# Sch_Lab_2.net
KiCad netlist of a schematic drawn in Altium Designer
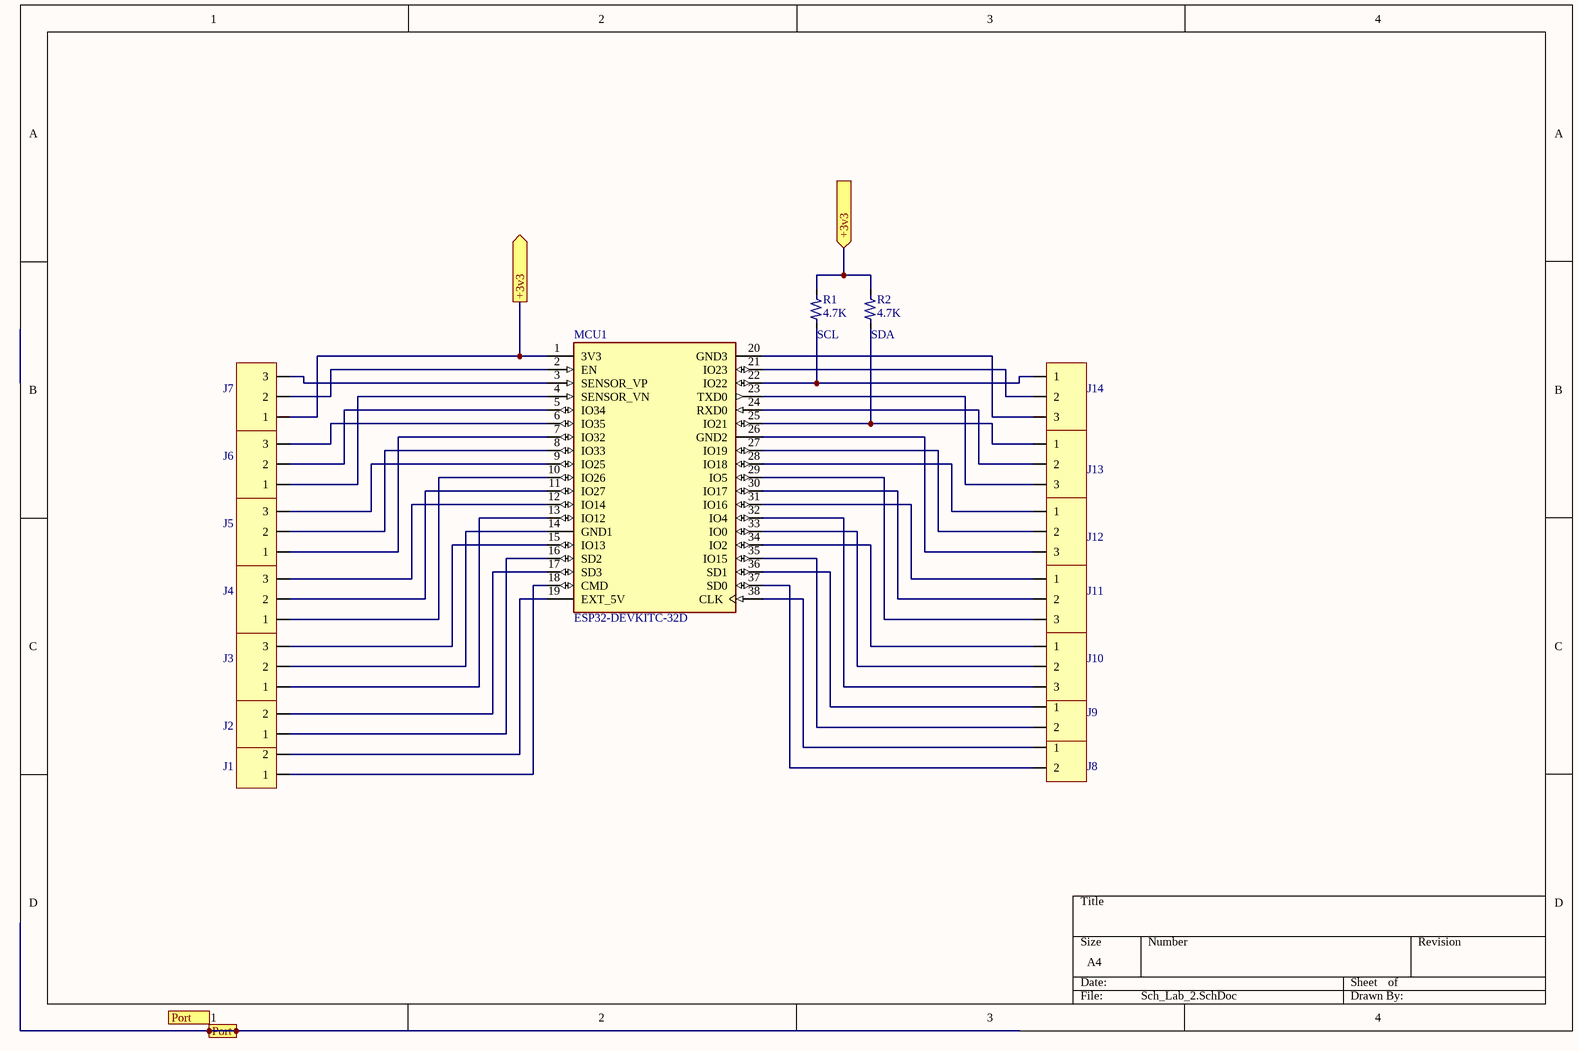
[diagram p0: Sch_Lab_2.SchDoc]

(export (version "E")
  (design (tool "Eeschema 10.0.6"))
  (components
    (comp (ref "J1") (value "~") (footprint "TB_200Mil 2 P") (libsource (lib "") (part "TB 2 PIN_1")))
    (comp (ref "J2") (value "~") (footprint "TB_200Mil 2 P") (libsource (lib "") (part "TB 2 PIN_1")))
    (comp (ref "J3") (value "~") (footprint "TB_200Mil 3 P") (libsource (lib "") (part "TB 3 PIN_1")))
    (comp (ref "J4") (value "~") (footprint "TB_200Mil 3 P") (libsource (lib "") (part "TB 3 PIN_1")))
    (comp (ref "J5") (value "~") (footprint "TB_200Mil 3 P") (libsource (lib "") (part "TB 3 PIN_1")))
    (comp (ref "J6") (value "~") (footprint "TB_200Mil 3 P") (libsource (lib "") (part "TB 3 PIN_1")))
    (comp (ref "J7") (value "~") (footprint "TB_200Mil 3 P") (libsource (lib "") (part "TB 3 PIN_1")))
    (comp (ref "J8")
      (value "~")
      (footprint "TB_200Mil 2 P")
      (libsource (lib "Library Connector") (part "TB 2 PIN"))
    )
    (comp (ref "J9")
      (value "~")
      (footprint "TB_200Mil 2 P")
      (libsource (lib "Library Connector") (part "TB 2 PIN"))
    )
    (comp (ref "J10")
      (value "~")
      (footprint "TB_200Mil 3 P")
      (libsource (lib "Library Connector") (part "TB 3 PIN"))
    )
    (comp (ref "J11")
      (value "~")
      (footprint "TB_200Mil 3 P")
      (libsource (lib "Library Connector") (part "TB 3 PIN"))
    )
    (comp (ref "J12")
      (value "~")
      (footprint "TB_200Mil 3 P")
      (libsource (lib "Library Connector") (part "TB 3 PIN"))
    )
    (comp (ref "J13")
      (value "~")
      (footprint "TB_200Mil 3 P")
      (libsource (lib "Library Connector") (part "TB 3 PIN"))
    )
    (comp (ref "J14")
      (value "~")
      (footprint "TB_200Mil 3 P")
      (libsource (lib "Library Connector") (part "TB 3 PIN"))
    )
    (comp (ref "MCU1")
      (value "ESP32-DEVKITC-32D")
      (footprint "MODULE_ESP32-DEVKITC-32D")
      (description "EVAL BOARD FOR ESP-WROOM-32")
      (fields (field (name "MF") "Espressif Systems"))
      (libsource (lib "ESP32-DEVKITC-32D") (part "ESP32-DEVKITC-32D"))
    )
    (comp (ref "R1") (value "4.7K") (footprint "4.7K") (libsource (lib "Library 0.25w 1_") (part "4.7K")))
    (comp (ref "R2") (value "4.7K") (footprint "4.7K") (libsource (lib "Library 0.25w 1_") (part "4.7K")))
  )
  (nets
    (net (code "1") (name "/+3v3") (class "Default")
      (node (ref "J7") (pin "1") (pinfunction "1_1") (pintype "passive"))
      (node (ref "MCU1") (pin "1") (pinfunction "3V3_1") (pintype "power_in"))
      (node (ref "R1") (pin "2") (pintype "passive"))
      (node (ref "R2") (pin "2") (pintype "passive"))
    )
    (net (code "3") (name "Net-(MCU1-CLK)") (class "Default")
      (node (ref "J8") (pin "1") (pinfunction "1_1") (pintype "passive"))
      (node (ref "MCU1") (pin "38") (pinfunction "CLK_38") (pintype "input"))
    )
    (net (code "4") (name "Net-(MCU1-CMD)") (class "Default")
      (node (ref "J1") (pin "1") (pinfunction "1_1") (pintype "passive"))
      (node (ref "MCU1") (pin "18") (pinfunction "CMD_18") (pintype "bidirectional"))
    )
    (net (code "5") (name "Net-(MCU1-EN)") (class "Default")
      (node (ref "J7") (pin "2") (pinfunction "2_2") (pintype "passive"))
      (node (ref "MCU1") (pin "2") (pinfunction "EN_2") (pintype "input"))
    )
    (net (code "6") (name "Net-(MCU1-EXT_5V)") (class "Default")
      (node (ref "J1") (pin "2") (pinfunction "2_2") (pintype "passive"))
      (node (ref "MCU1") (pin "19") (pinfunction "EXT_5V_19") (pintype "power_in"))
    )
    (net (code "7") (name "Net-(MCU1-GND1)") (class "Default")
      (node (ref "J3") (pin "2") (pinfunction "2_2") (pintype "passive"))
      (node (ref "MCU1") (pin "14") (pinfunction "GND1_14") (pintype "power_in"))
    )
    (net (code "8") (name "Net-(MCU1-GND2)") (class "Default")
      (node (ref "J12") (pin "3") (pinfunction "3_3") (pintype "passive"))
      (node (ref "MCU1") (pin "26") (pinfunction "GND2_26") (pintype "power_in"))
    )
    (net (code "9") (name "Net-(MCU1-GND3)") (class "Default")
      (node (ref "J14") (pin "3") (pinfunction "3_3") (pintype "passive"))
      (node (ref "MCU1") (pin "20") (pinfunction "GND3_20") (pintype "power_in"))
    )
    (net (code "10") (name "Net-(MCU1-IO0)") (class "Default")
      (node (ref "J10") (pin "2") (pinfunction "2_2") (pintype "passive"))
      (node (ref "MCU1") (pin "33") (pinfunction "IO0_33") (pintype "bidirectional"))
    )
    (net (code "11") (name "Net-(MCU1-IO2)") (class "Default")
      (node (ref "J10") (pin "1") (pinfunction "1_1") (pintype "passive"))
      (node (ref "MCU1") (pin "34") (pinfunction "IO2_34") (pintype "bidirectional"))
    )
    (net (code "12") (name "Net-(MCU1-IO4)") (class "Default")
      (node (ref "J10") (pin "3") (pinfunction "3_3") (pintype "passive"))
      (node (ref "MCU1") (pin "32") (pinfunction "IO4_32") (pintype "bidirectional"))
    )
    (net (code "13") (name "Net-(MCU1-IO5)") (class "Default")
      (node (ref "J11") (pin "3") (pinfunction "3_3") (pintype "passive"))
      (node (ref "MCU1") (pin "29") (pinfunction "IO5_29") (pintype "bidirectional"))
    )
    (net (code "14") (name "Net-(MCU1-IO12)") (class "Default")
      (node (ref "J3") (pin "1") (pinfunction "1_1") (pintype "passive"))
      (node (ref "MCU1") (pin "13") (pinfunction "IO12_13") (pintype "bidirectional"))
    )
    (net (code "15") (name "Net-(MCU1-IO13)") (class "Default")
      (node (ref "J3") (pin "3") (pinfunction "3_3") (pintype "passive"))
      (node (ref "MCU1") (pin "15") (pinfunction "IO13_15") (pintype "bidirectional"))
    )
    (net (code "16") (name "Net-(MCU1-IO14)") (class "Default")
      (node (ref "J4") (pin "3") (pinfunction "3_3") (pintype "passive"))
      (node (ref "MCU1") (pin "12") (pinfunction "IO14_12") (pintype "bidirectional"))
    )
    (net (code "17") (name "Net-(MCU1-IO15)") (class "Default")
      (node (ref "J9") (pin "2") (pinfunction "2_2") (pintype "passive"))
      (node (ref "MCU1") (pin "35") (pinfunction "IO15_35") (pintype "bidirectional"))
    )
    (net (code "18") (name "Net-(MCU1-IO16)") (class "Default")
      (node (ref "J11") (pin "1") (pinfunction "1_1") (pintype "passive"))
      (node (ref "MCU1") (pin "31") (pinfunction "IO16_31") (pintype "bidirectional"))
    )
    (net (code "19") (name "Net-(MCU1-IO17)") (class "Default")
      (node (ref "J11") (pin "2") (pinfunction "2_2") (pintype "passive"))
      (node (ref "MCU1") (pin "30") (pinfunction "IO17_30") (pintype "bidirectional"))
    )
    (net (code "20") (name "Net-(MCU1-IO18)") (class "Default")
      (node (ref "J12") (pin "1") (pinfunction "1_1") (pintype "passive"))
      (node (ref "MCU1") (pin "28") (pinfunction "IO18_28") (pintype "bidirectional"))
    )
    (net (code "21") (name "Net-(MCU1-IO19)") (class "Default")
      (node (ref "J12") (pin "2") (pinfunction "2_2") (pintype "passive"))
      (node (ref "MCU1") (pin "27") (pinfunction "IO19_27") (pintype "bidirectional"))
    )
    (net (code "22") (name "Net-(MCU1-IO21)") (class "Default")
      (node (ref "J13") (pin "1") (pinfunction "1_1") (pintype "passive"))
      (node (ref "MCU1") (pin "25") (pinfunction "IO21_25") (pintype "bidirectional"))
      (node (ref "R2") (pin "1") (pintype "passive"))
    )
    (net (code "23") (name "Net-(MCU1-IO22)") (class "Default")
      (node (ref "J14") (pin "1") (pinfunction "1_1") (pintype "passive"))
      (node (ref "MCU1") (pin "22") (pinfunction "IO22_22") (pintype "bidirectional"))
      (node (ref "R1") (pin "1") (pintype "passive"))
    )
    (net (code "24") (name "Net-(MCU1-IO23)") (class "Default")
      (node (ref "J14") (pin "2") (pinfunction "2_2") (pintype "passive"))
      (node (ref "MCU1") (pin "21") (pinfunction "IO23_21") (pintype "bidirectional"))
    )
    (net (code "25") (name "Net-(MCU1-IO25)") (class "Default")
      (node (ref "J5") (pin "3") (pinfunction "3_3") (pintype "passive"))
      (node (ref "MCU1") (pin "9") (pinfunction "IO25_9") (pintype "bidirectional"))
    )
    (net (code "26") (name "Net-(MCU1-IO26)") (class "Default")
      (node (ref "J4") (pin "1") (pinfunction "1_1") (pintype "passive"))
      (node (ref "MCU1") (pin "10") (pinfunction "IO26_10") (pintype "bidirectional"))
    )
    (net (code "27") (name "Net-(MCU1-IO27)") (class "Default")
      (node (ref "J4") (pin "2") (pinfunction "2_2") (pintype "passive"))
      (node (ref "MCU1") (pin "11") (pinfunction "IO27_11") (pintype "bidirectional"))
    )
    (net (code "28") (name "Net-(MCU1-IO32)") (class "Default")
      (node (ref "J5") (pin "1") (pinfunction "1_1") (pintype "passive"))
      (node (ref "MCU1") (pin "7") (pinfunction "IO32_7") (pintype "bidirectional"))
    )
    (net (code "29") (name "Net-(MCU1-IO33)") (class "Default")
      (node (ref "J5") (pin "2") (pinfunction "2_2") (pintype "passive"))
      (node (ref "MCU1") (pin "8") (pinfunction "IO33_8") (pintype "bidirectional"))
    )
    (net (code "30") (name "Net-(MCU1-IO34)") (class "Default")
      (node (ref "J6") (pin "2") (pinfunction "2_2") (pintype "passive"))
      (node (ref "MCU1") (pin "5") (pinfunction "IO34_5") (pintype "bidirectional"))
    )
    (net (code "31") (name "Net-(MCU1-IO35)") (class "Default")
      (node (ref "J6") (pin "3") (pinfunction "3_3") (pintype "passive"))
      (node (ref "MCU1") (pin "6") (pinfunction "IO35_6") (pintype "bidirectional"))
    )
    (net (code "32") (name "Net-(MCU1-RXD0)") (class "Default")
      (node (ref "J13") (pin "2") (pinfunction "2_2") (pintype "passive"))
      (node (ref "MCU1") (pin "24") (pinfunction "RXD0_24") (pintype "input"))
    )
    (net (code "33") (name "Net-(MCU1-SD0)") (class "Default")
      (node (ref "J8") (pin "2") (pinfunction "2_2") (pintype "passive"))
      (node (ref "MCU1") (pin "37") (pinfunction "SD0_37") (pintype "bidirectional"))
    )
    (net (code "34") (name "Net-(MCU1-SD1)") (class "Default")
      (node (ref "J9") (pin "1") (pinfunction "1_1") (pintype "passive"))
      (node (ref "MCU1") (pin "36") (pinfunction "SD1_36") (pintype "bidirectional"))
    )
    (net (code "35") (name "Net-(MCU1-SD2)") (class "Default")
      (node (ref "J2") (pin "1") (pinfunction "1_1") (pintype "passive"))
      (node (ref "MCU1") (pin "16") (pinfunction "SD2_16") (pintype "bidirectional"))
    )
    (net (code "36") (name "Net-(MCU1-SD3)") (class "Default")
      (node (ref "J2") (pin "2") (pinfunction "2_2") (pintype "passive"))
      (node (ref "MCU1") (pin "17") (pinfunction "SD3_17") (pintype "bidirectional"))
    )
    (net (code "37") (name "Net-(MCU1-SENSOR_VN)") (class "Default")
      (node (ref "J6") (pin "1") (pinfunction "1_1") (pintype "passive"))
      (node (ref "MCU1") (pin "4") (pinfunction "SENSOR_VN_4") (pintype "input"))
    )
    (net (code "38") (name "Net-(MCU1-SENSOR_VP)") (class "Default")
      (node (ref "J7") (pin "3") (pinfunction "3_3") (pintype "passive"))
      (node (ref "MCU1") (pin "3") (pinfunction "SENSOR_VP_3") (pintype "input"))
    )
    (net (code "39") (name "Net-(MCU1-TXD0)") (class "Default")
      (node (ref "J13") (pin "3") (pinfunction "3_3") (pintype "passive"))
      (node (ref "MCU1") (pin "23") (pinfunction "TXD0_23") (pintype "output"))
    )
  )
)
